# Integrated_Main_Driver_Board-01-Minimum_.net
KiCad netlist of a schematic drawn in Altium Designer
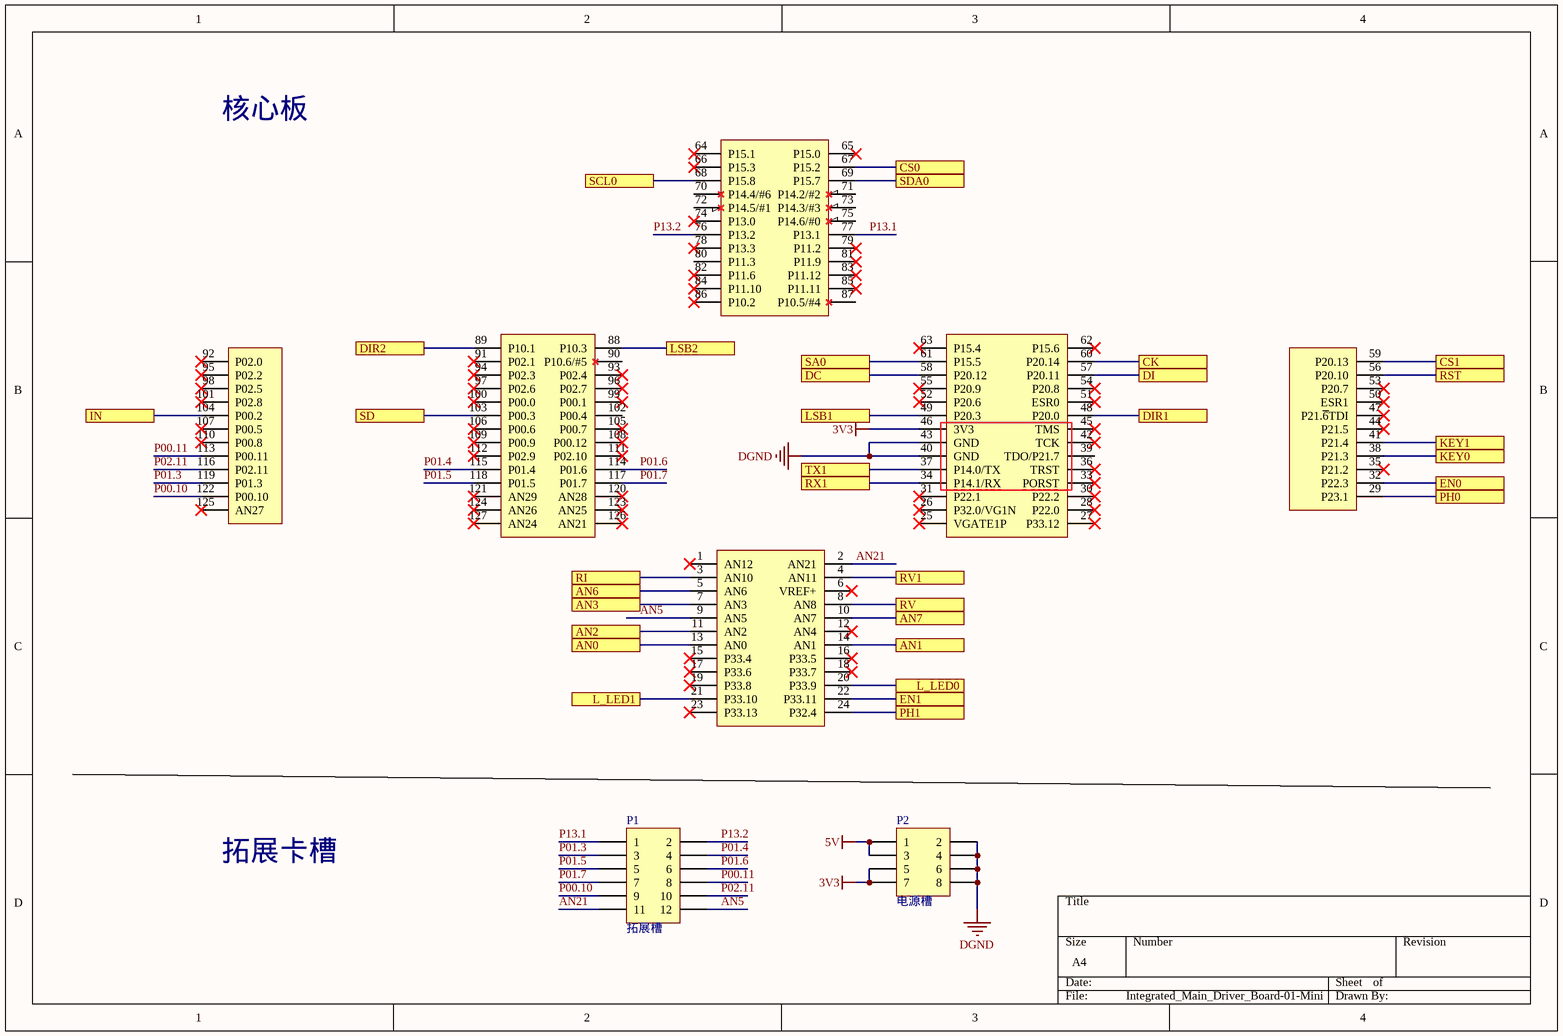
[diagram p0: Integrated_Main_Driver_Board-01-Minimum System Circuit-20230110.SchDoc]

(export (version "E")
  (design (tool "Eeschema 10.0.6"))
  (components
    (comp (ref "LQ-TC1")
      (value "LQ-TC3X7-SYSVB")
      (footprint "TC377")
      (libsource (lib "Schlib1") (part "LQ-TC3X7-SYSVB"))
    )
    (comp (ref "P1")
      (value "拓展槽")
      (footprint "HDR2X6")
      (description "Header, 6-Pin, Dual row")
      (fields (field (name "PUBLISHER") "Altium Limited"))
      (libsource (lib "Miscellaneous Connectors") (part "Header 6X2"))
    )
    (comp (ref "P2")
      (value "电源槽")
      (footprint "HDR2X4")
      (description "Header, 4-Pin, Dual row")
      (fields (field (name "PUBLISHER") "Altium Limited"))
      (libsource (lib "Miscellaneous Connectors") (part "Header 4X2"))
    )
  )
  (nets
    (net (code "1") (name "/AN0") (class "Default")
      (node (ref "LQ-TC1") (pin "13") (pinfunction "AN0_13") (pintype "passive"))
    )
    (net (code "2") (name "/AN1") (class "Default")
      (node (ref "LQ-TC1") (pin "14") (pinfunction "AN1_14") (pintype "passive"))
    )
    (net (code "3") (name "/AN2") (class "Default")
      (node (ref "LQ-TC1") (pin "11") (pinfunction "AN2_11") (pintype "passive"))
    )
    (net (code "4") (name "/AN3") (class "Default")
      (node (ref "LQ-TC1") (pin "7") (pinfunction "AN3_7") (pintype "passive"))
    )
    (net (code "5") (name "/AN5") (class "Default")
      (node (ref "LQ-TC1") (pin "9") (pinfunction "AN5_9") (pintype "passive"))
      (node (ref "P1") (pin "12") (pinfunction "12_12") (pintype "passive"))
    )
    (net (code "6") (name "/AN6") (class "Default")
      (node (ref "LQ-TC1") (pin "5") (pinfunction "AN6_5") (pintype "passive"))
    )
    (net (code "7") (name "/AN7") (class "Default")
      (node (ref "LQ-TC1") (pin "10") (pinfunction "AN7_10") (pintype "passive"))
    )
    (net (code "8") (name "/AN21") (class "Default")
      (node (ref "LQ-TC1") (pin "2") (pinfunction "AN21_2") (pintype "passive"))
      (node (ref "P1") (pin "11") (pinfunction "11_11") (pintype "passive"))
    )
    (net (code "9") (name "/CK") (class "Default")
      (node (ref "LQ-TC1") (pin "60") (pinfunction "P20.14_60") (pintype "passive"))
    )
    (net (code "10") (name "/CS0") (class "Default")
      (node (ref "LQ-TC1") (pin "67") (pinfunction "P15.2_67") (pintype "passive"))
    )
    (net (code "11") (name "/CS1") (class "Default")
      (node (ref "LQ-TC1") (pin "59") (pinfunction "P20.13_59") (pintype "passive"))
    )
    (net (code "12") (name "/DC") (class "Default")
      (node (ref "LQ-TC1") (pin "58") (pinfunction "P20.12_58") (pintype "passive"))
    )
    (net (code "13") (name "/DI") (class "Default")
      (node (ref "LQ-TC1") (pin "57") (pinfunction "P20.11_57") (pintype "passive"))
    )
    (net (code "14") (name "/DIR1") (class "Default")
      (node (ref "LQ-TC1") (pin "48") (pinfunction "P20.0_48") (pintype "passive"))
    )
    (net (code "15") (name "/DIR2") (class "Default")
      (node (ref "LQ-TC1") (pin "89") (pinfunction "P10.1_89") (pintype "passive"))
    )
    (net (code "16") (name "/EN0") (class "Default")
      (node (ref "LQ-TC1") (pin "32") (pinfunction "P22.3_32") (pintype "passive"))
    )
    (net (code "17") (name "/EN1") (class "Default")
      (node (ref "LQ-TC1") (pin "22") (pinfunction "P33.11_22") (pintype "passive"))
    )
    (net (code "18") (name "/IN") (class "Default")
      (node (ref "LQ-TC1") (pin "104") (pinfunction "P00.2_104") (pintype "passive"))
    )
    (net (code "19") (name "/KEY0") (class "Default")
      (node (ref "LQ-TC1") (pin "38") (pinfunction "P21.3_38") (pintype "passive"))
    )
    (net (code "20") (name "/KEY1") (class "Default")
      (node (ref "LQ-TC1") (pin "41") (pinfunction "P21.4_41") (pintype "passive"))
    )
    (net (code "21") (name "/LSB1") (class "Default")
      (node (ref "LQ-TC1") (pin "49") (pinfunction "P20.3_49") (pintype "passive"))
    )
    (net (code "22") (name "/LSB2") (class "Default")
      (node (ref "LQ-TC1") (pin "88") (pinfunction "P10.3_88") (pintype "passive"))
    )
    (net (code "23") (name "/L_LED0") (class "Default")
      (node (ref "LQ-TC1") (pin "20") (pinfunction "P33.9_20") (pintype "passive"))
    )
    (net (code "24") (name "/L_LED1") (class "Default")
      (node (ref "LQ-TC1") (pin "21") (pinfunction "P33.10_21") (pintype "passive"))
    )
    (net (code "25") (name "/P00.10") (class "Default")
      (node (ref "LQ-TC1") (pin "122") (pinfunction "P00.10_122") (pintype "passive"))
      (node (ref "P1") (pin "9") (pinfunction "9_9") (pintype "passive"))
    )
    (net (code "26") (name "/P00.11") (class "Default")
      (node (ref "LQ-TC1") (pin "113") (pinfunction "P00.11_113") (pintype "passive"))
      (node (ref "P1") (pin "8") (pinfunction "8_8") (pintype "passive"))
    )
    (net (code "27") (name "/P01.3") (class "Default")
      (node (ref "LQ-TC1") (pin "119") (pinfunction "P01.3_119") (pintype "passive"))
      (node (ref "P1") (pin "3") (pinfunction "3_3") (pintype "passive"))
    )
    (net (code "28") (name "/P01.4") (class "Default")
      (node (ref "LQ-TC1") (pin "115") (pinfunction "P01.4_115") (pintype "passive"))
      (node (ref "P1") (pin "4") (pinfunction "4_4") (pintype "passive"))
    )
    (net (code "29") (name "/P01.5") (class "Default")
      (node (ref "LQ-TC1") (pin "118") (pinfunction "P01.5_118") (pintype "passive"))
      (node (ref "P1") (pin "5") (pinfunction "5_5") (pintype "passive"))
    )
    (net (code "30") (name "/P01.6") (class "Default")
      (node (ref "LQ-TC1") (pin "114") (pinfunction "P01.6_114") (pintype "passive"))
      (node (ref "P1") (pin "6") (pinfunction "6_6") (pintype "passive"))
    )
    (net (code "31") (name "/P01.7") (class "Default")
      (node (ref "LQ-TC1") (pin "117") (pinfunction "P01.7_117") (pintype "passive"))
      (node (ref "P1") (pin "7") (pinfunction "7_7") (pintype "passive"))
    )
    (net (code "32") (name "/P02.11") (class "Default")
      (node (ref "LQ-TC1") (pin "116") (pinfunction "P02.11_116") (pintype "passive"))
      (node (ref "P1") (pin "10") (pinfunction "10_10") (pintype "passive"))
    )
    (net (code "33") (name "/P13.1") (class "Default")
      (node (ref "LQ-TC1") (pin "77") (pinfunction "P13.1_77") (pintype "passive"))
      (node (ref "P1") (pin "1") (pinfunction "1_1") (pintype "passive"))
    )
    (net (code "34") (name "/P13.2") (class "Default")
      (node (ref "LQ-TC1") (pin "76") (pinfunction "P13.2_76") (pintype "passive"))
      (node (ref "P1") (pin "2") (pinfunction "2_2") (pintype "passive"))
    )
    (net (code "35") (name "/PH0") (class "Default")
      (node (ref "LQ-TC1") (pin "29") (pinfunction "P23.1_29") (pintype "passive"))
    )
    (net (code "36") (name "/PH1") (class "Default")
      (node (ref "LQ-TC1") (pin "24") (pinfunction "P32.4_24") (pintype "passive"))
    )
    (net (code "37") (name "/RI") (class "Default")
      (node (ref "LQ-TC1") (pin "3") (pinfunction "AN10_3") (pintype "passive"))
    )
    (net (code "38") (name "/RST") (class "Default")
      (node (ref "LQ-TC1") (pin "56") (pinfunction "P20.10_56") (pintype "passive"))
    )
    (net (code "39") (name "/RV") (class "Default")
      (node (ref "LQ-TC1") (pin "8") (pinfunction "AN8_8") (pintype "passive"))
    )
    (net (code "40") (name "/RV1") (class "Default")
      (node (ref "LQ-TC1") (pin "4") (pinfunction "AN11_4") (pintype "passive"))
    )
    (net (code "41") (name "/RX1") (class "Default")
      (node (ref "LQ-TC1") (pin "34") (pinfunction "P14.1/RX_34") (pintype "passive"))
    )
    (net (code "42") (name "/SA0") (class "Default")
      (node (ref "LQ-TC1") (pin "61") (pinfunction "P15.5_61") (pintype "passive"))
    )
    (net (code "43") (name "/SCL0") (class "Default")
      (node (ref "LQ-TC1") (pin "68") (pinfunction "P15.8_68") (pintype "passive"))
    )
    (net (code "44") (name "/SD") (class "Default")
      (node (ref "LQ-TC1") (pin "103") (pinfunction "P00.3_103") (pintype "passive"))
    )
    (net (code "45") (name "/SDA0") (class "Default")
      (node (ref "LQ-TC1") (pin "69") (pinfunction "P15.7_69") (pintype "passive"))
    )
    (net (code "46") (name "/TX1") (class "Default")
      (node (ref "LQ-TC1") (pin "37") (pinfunction "P14.0/TX_37") (pintype "passive"))
    )
    (net (code "47") (name "3V3") (class "Default")
      (node (ref "LQ-TC1") (pin "46") (pinfunction "3V3_46") (pintype "passive"))
      (node (ref "P2") (pin "5") (pinfunction "5_5") (pintype "passive"))
      (node (ref "P2") (pin "7") (pinfunction "7_7") (pintype "passive"))
    )
    (net (code "48") (name "5V") (class "Default")
      (node (ref "P2") (pin "1") (pinfunction "1_1") (pintype "passive"))
      (node (ref "P2") (pin "3") (pinfunction "3_3") (pintype "passive"))
    )
    (net (code "49") (name "DGND") (class "Default")
      (node (ref "LQ-TC1") (pin "40") (pinfunction "GND_40") (pintype "passive"))
      (node (ref "LQ-TC1") (pin "43") (pinfunction "GND_43") (pintype "passive"))
      (node (ref "P2") (pin "2") (pinfunction "2_2") (pintype "passive"))
      (node (ref "P2") (pin "4") (pinfunction "4_4") (pintype "passive"))
      (node (ref "P2") (pin "6") (pinfunction "6_6") (pintype "passive"))
      (node (ref "P2") (pin "8") (pinfunction "8_8") (pintype "passive"))
    )
    (net (code "50") (name "unconnected-(LQ-TC1-AN4-Pad12)") (class "Default")
      (node (ref "LQ-TC1") (pin "12") (pinfunction "AN4_12") (pintype "passive+no_connect"))
    )
    (net (code "51") (name "unconnected-(LQ-TC1-AN12-Pad1)") (class "Default")
      (node (ref "LQ-TC1") (pin "1") (pinfunction "AN12_1") (pintype "passive+no_connect"))
    )
    (net (code "52") (name "unconnected-(LQ-TC1-AN21-Pad126)") (class "Default")
      (node (ref "LQ-TC1") (pin "126") (pinfunction "AN21_126") (pintype "passive+no_connect"))
    )
    (net (code "53") (name "unconnected-(LQ-TC1-AN24-Pad127)") (class "Default")
      (node (ref "LQ-TC1") (pin "127") (pinfunction "AN24_127") (pintype "passive+no_connect"))
    )
    (net (code "54") (name "unconnected-(LQ-TC1-AN25-Pad123)") (class "Default")
      (node (ref "LQ-TC1") (pin "123") (pinfunction "AN25_123") (pintype "passive+no_connect"))
    )
    (net (code "55") (name "unconnected-(LQ-TC1-AN26-Pad124)") (class "Default")
      (node (ref "LQ-TC1") (pin "124") (pinfunction "AN26_124") (pintype "passive+no_connect"))
    )
    (net (code "56") (name "unconnected-(LQ-TC1-AN27-Pad125)") (class "Default")
      (node (ref "LQ-TC1") (pin "125") (pinfunction "AN27_125") (pintype "passive+no_connect"))
    )
    (net (code "57") (name "unconnected-(LQ-TC1-AN28-Pad120)") (class "Default")
      (node (ref "LQ-TC1") (pin "120") (pinfunction "AN28_120") (pintype "passive+no_connect"))
    )
    (net (code "58") (name "unconnected-(LQ-TC1-AN29-Pad121)") (class "Default")
      (node (ref "LQ-TC1") (pin "121") (pinfunction "AN29_121") (pintype "passive+no_connect"))
    )
    (net (code "59") (name "unconnected-(LQ-TC1-ESR0-Pad51)") (class "Default")
      (node (ref "LQ-TC1") (pin "51") (pinfunction "ESR0_51") (pintype "passive+no_connect"))
    )
    (net (code "60") (name "unconnected-(LQ-TC1-ESR1-Pad50)") (class "Default")
      (node (ref "LQ-TC1") (pin "50") (pinfunction "ESR1_50") (pintype "passive+no_connect"))
    )
    (net (code "61") (name "unconnected-(LQ-TC1-P00.0-Pad100)") (class "Default")
      (node (ref "LQ-TC1") (pin "100") (pinfunction "P00.0_100") (pintype "passive+no_connect"))
    )
    (net (code "62") (name "unconnected-(LQ-TC1-P00.1-Pad99)") (class "Default")
      (node (ref "LQ-TC1") (pin "99") (pinfunction "P00.1_99") (pintype "passive+no_connect"))
    )
    (net (code "63") (name "unconnected-(LQ-TC1-P00.4-Pad102)") (class "Default")
      (node (ref "LQ-TC1") (pin "102") (pinfunction "P00.4_102") (pintype "passive"))
    )
    (net (code "64") (name "unconnected-(LQ-TC1-P00.5-Pad107)") (class "Default")
      (node (ref "LQ-TC1") (pin "107") (pinfunction "P00.5_107") (pintype "passive+no_connect"))
    )
    (net (code "65") (name "unconnected-(LQ-TC1-P00.6-Pad106)") (class "Default")
      (node (ref "LQ-TC1") (pin "106") (pinfunction "P00.6_106") (pintype "passive+no_connect"))
    )
    (net (code "66") (name "unconnected-(LQ-TC1-P00.7-Pad105)") (class "Default")
      (node (ref "LQ-TC1") (pin "105") (pinfunction "P00.7_105") (pintype "passive+no_connect"))
    )
    (net (code "67") (name "unconnected-(LQ-TC1-P00.8-Pad110)") (class "Default")
      (node (ref "LQ-TC1") (pin "110") (pinfunction "P00.8_110") (pintype "passive+no_connect"))
    )
    (net (code "68") (name "unconnected-(LQ-TC1-P00.9-Pad109)") (class "Default")
      (node (ref "LQ-TC1") (pin "109") (pinfunction "P00.9_109") (pintype "passive+no_connect"))
    )
    (net (code "69") (name "unconnected-(LQ-TC1-P00.12-Pad108)") (class "Default")
      (node (ref "LQ-TC1") (pin "108") (pinfunction "P00.12_108") (pintype "passive+no_connect"))
    )
    (net (code "70") (name "unconnected-(LQ-TC1-P02.0-Pad92)") (class "Default")
      (node (ref "LQ-TC1") (pin "92") (pinfunction "P02.0_92") (pintype "passive+no_connect"))
    )
    (net (code "71") (name "unconnected-(LQ-TC1-P02.1-Pad91)") (class "Default")
      (node (ref "LQ-TC1") (pin "91") (pinfunction "P02.1_91") (pintype "passive+no_connect"))
    )
    (net (code "72") (name "unconnected-(LQ-TC1-P02.2-Pad95)") (class "Default")
      (node (ref "LQ-TC1") (pin "95") (pinfunction "P02.2_95") (pintype "passive+no_connect"))
    )
    (net (code "73") (name "unconnected-(LQ-TC1-P02.3-Pad94)") (class "Default")
      (node (ref "LQ-TC1") (pin "94") (pinfunction "P02.3_94") (pintype "passive+no_connect"))
    )
    (net (code "74") (name "unconnected-(LQ-TC1-P02.4-Pad93)") (class "Default")
      (node (ref "LQ-TC1") (pin "93") (pinfunction "P02.4_93") (pintype "passive+no_connect"))
    )
    (net (code "75") (name "unconnected-(LQ-TC1-P02.5-Pad98)") (class "Default")
      (node (ref "LQ-TC1") (pin "98") (pinfunction "P02.5_98") (pintype "passive+no_connect"))
    )
    (net (code "76") (name "unconnected-(LQ-TC1-P02.6-Pad97)") (class "Default")
      (node (ref "LQ-TC1") (pin "97") (pinfunction "P02.6_97") (pintype "passive+no_connect"))
    )
    (net (code "77") (name "unconnected-(LQ-TC1-P02.7-Pad96)") (class "Default")
      (node (ref "LQ-TC1") (pin "96") (pinfunction "P02.7_96") (pintype "passive+no_connect"))
    )
    (net (code "78") (name "unconnected-(LQ-TC1-P02.8-Pad101)") (class "Default")
      (node (ref "LQ-TC1") (pin "101") (pinfunction "P02.8_101") (pintype "passive+no_connect"))
    )
    (net (code "79") (name "unconnected-(LQ-TC1-P02.9-Pad112)") (class "Default")
      (node (ref "LQ-TC1") (pin "112") (pinfunction "P02.9_112") (pintype "passive+no_connect"))
    )
    (net (code "80") (name "unconnected-(LQ-TC1-P02.10-Pad111)") (class "Default")
      (node (ref "LQ-TC1") (pin "111") (pinfunction "P02.10_111") (pintype "passive+no_connect"))
    )
    (net (code "81") (name "unconnected-(LQ-TC1-P10.2-Pad86)") (class "Default")
      (node (ref "LQ-TC1") (pin "86") (pinfunction "P10.2_86") (pintype "passive+no_connect"))
    )
    (net (code "82") (name "unconnected-(LQ-TC1-P10.5{slash}#4-Pad87)") (class "Default")
      (node (ref "LQ-TC1") (pin "87") (pinfunction "P10.5/#4_87") (pintype "passive"))
    )
    (net (code "83") (name "unconnected-(LQ-TC1-P10.6{slash}#5-Pad90)") (class "Default")
      (node (ref "LQ-TC1") (pin "90") (pinfunction "P10.6/#5_90") (pintype "passive"))
    )
    (net (code "84") (name "unconnected-(LQ-TC1-P11.2-Pad79)") (class "Default")
      (node (ref "LQ-TC1") (pin "79") (pinfunction "P11.2_79") (pintype "passive+no_connect"))
    )
    (net (code "85") (name "unconnected-(LQ-TC1-P11.3-Pad80)") (class "Default")
      (node (ref "LQ-TC1") (pin "80") (pinfunction "P11.3_80") (pintype "passive"))
    )
    (net (code "86") (name "unconnected-(LQ-TC1-P11.6-Pad82)") (class "Default")
      (node (ref "LQ-TC1") (pin "82") (pinfunction "P11.6_82") (pintype "passive+no_connect"))
    )
    (net (code "87") (name "unconnected-(LQ-TC1-P11.9-Pad81)") (class "Default")
      (node (ref "LQ-TC1") (pin "81") (pinfunction "P11.9_81") (pintype "passive+no_connect"))
    )
    (net (code "88") (name "unconnected-(LQ-TC1-P11.10-Pad84)") (class "Default")
      (node (ref "LQ-TC1") (pin "84") (pinfunction "P11.10_84") (pintype "passive+no_connect"))
    )
    (net (code "89") (name "unconnected-(LQ-TC1-P11.11-Pad85)") (class "Default")
      (node (ref "LQ-TC1") (pin "85") (pinfunction "P11.11_85") (pintype "passive+no_connect"))
    )
    (net (code "90") (name "unconnected-(LQ-TC1-P11.12-Pad83)") (class "Default")
      (node (ref "LQ-TC1") (pin "83") (pinfunction "P11.12_83") (pintype "passive+no_connect"))
    )
    (net (code "91") (name "unconnected-(LQ-TC1-P13.0-Pad74)") (class "Default")
      (node (ref "LQ-TC1") (pin "74") (pinfunction "P13.0_74") (pintype "passive+no_connect"))
    )
    (net (code "92") (name "unconnected-(LQ-TC1-P13.3-Pad78)") (class "Default")
      (node (ref "LQ-TC1") (pin "78") (pinfunction "P13.3_78") (pintype "passive+no_connect"))
    )
    (net (code "93") (name "unconnected-(LQ-TC1-P14.2{slash}#2-Pad71)") (class "Default")
      (node (ref "LQ-TC1") (pin "71") (pinfunction "P14.2/#2_71") (pintype "passive"))
    )
    (net (code "94") (name "unconnected-(LQ-TC1-P14.3{slash}#3-Pad73)") (class "Default")
      (node (ref "LQ-TC1") (pin "73") (pinfunction "P14.3/#3_73") (pintype "passive"))
    )
    (net (code "95") (name "unconnected-(LQ-TC1-P14.4{slash}#6-Pad70)") (class "Default")
      (node (ref "LQ-TC1") (pin "70") (pinfunction "P14.4/#6_70") (pintype "passive"))
    )
    (net (code "96") (name "unconnected-(LQ-TC1-P14.5{slash}#1-Pad72)") (class "Default")
      (node (ref "LQ-TC1") (pin "72") (pinfunction "P14.5/#1_72") (pintype "passive"))
    )
    (net (code "97") (name "unconnected-(LQ-TC1-P14.6{slash}#0-Pad75)") (class "Default")
      (node (ref "LQ-TC1") (pin "75") (pinfunction "P14.6/#0_75") (pintype "passive"))
    )
    (net (code "98") (name "unconnected-(LQ-TC1-P15.0-Pad65)") (class "Default")
      (node (ref "LQ-TC1") (pin "65") (pinfunction "P15.0_65") (pintype "passive+no_connect"))
    )
    (net (code "99") (name "unconnected-(LQ-TC1-P15.1-Pad64)") (class "Default")
      (node (ref "LQ-TC1") (pin "64") (pinfunction "P15.1_64") (pintype "passive+no_connect"))
    )
    (net (code "100") (name "unconnected-(LQ-TC1-P15.3-Pad66)") (class "Default")
      (node (ref "LQ-TC1") (pin "66") (pinfunction "P15.3_66") (pintype "passive+no_connect"))
    )
    (net (code "101") (name "unconnected-(LQ-TC1-P15.4-Pad63)") (class "Default")
      (node (ref "LQ-TC1") (pin "63") (pinfunction "P15.4_63") (pintype "passive+no_connect"))
    )
    (net (code "102") (name "unconnected-(LQ-TC1-P15.6-Pad62)") (class "Default")
      (node (ref "LQ-TC1") (pin "62") (pinfunction "P15.6_62") (pintype "passive+no_connect"))
    )
    (net (code "103") (name "unconnected-(LQ-TC1-P20.6-Pad52)") (class "Default")
      (node (ref "LQ-TC1") (pin "52") (pinfunction "P20.6_52") (pintype "passive+no_connect"))
    )
    (net (code "104") (name "unconnected-(LQ-TC1-P20.7-Pad53)") (class "Default")
      (node (ref "LQ-TC1") (pin "53") (pinfunction "P20.7_53") (pintype "passive+no_connect"))
    )
    (net (code "105") (name "unconnected-(LQ-TC1-P20.8-Pad54)") (class "Default")
      (node (ref "LQ-TC1") (pin "54") (pinfunction "P20.8_54") (pintype "passive+no_connect"))
    )
    (net (code "106") (name "unconnected-(LQ-TC1-P20.9-Pad55)") (class "Default")
      (node (ref "LQ-TC1") (pin "55") (pinfunction "P20.9_55") (pintype "passive+no_connect"))
    )
    (net (code "107") (name "unconnected-(LQ-TC1-P21.2-Pad35)") (class "Default")
      (node (ref "LQ-TC1") (pin "35") (pinfunction "P21.2_35") (pintype "passive+no_connect"))
    )
    (net (code "108") (name "unconnected-(LQ-TC1-P21.5-Pad44)") (class "Default")
      (node (ref "LQ-TC1") (pin "44") (pinfunction "P21.5_44") (pintype "passive+no_connect"))
    )
    (net (code "109") (name "unconnected-(LQ-TC1-P21.~{6}TDI-Pad47)") (class "Default")
      (node (ref "LQ-TC1") (pin "47") (pinfunction "P21.~{6}TDI_47") (pintype "passive+no_connect"))
    )
    (net (code "110") (name "unconnected-(LQ-TC1-P22.0-Pad28)") (class "Default")
      (node (ref "LQ-TC1") (pin "28") (pinfunction "P22.0_28") (pintype "passive+no_connect"))
    )
    (net (code "111") (name "unconnected-(LQ-TC1-P22.1-Pad31)") (class "Default")
      (node (ref "LQ-TC1") (pin "31") (pinfunction "P22.1_31") (pintype "passive+no_connect"))
    )
    (net (code "112") (name "unconnected-(LQ-TC1-P22.2-Pad30)") (class "Default")
      (node (ref "LQ-TC1") (pin "30") (pinfunction "P22.2_30") (pintype "passive+no_connect"))
    )
    (net (code "113") (name "unconnected-(LQ-TC1-P32.0{slash}VG1N-Pad26)") (class "Default")
      (node (ref "LQ-TC1") (pin "26") (pinfunction "P32.0/VG1N_26") (pintype "passive+no_connect"))
    )
    (net (code "114") (name "unconnected-(LQ-TC1-P33.4-Pad15)") (class "Default")
      (node (ref "LQ-TC1") (pin "15") (pinfunction "P33.4_15") (pintype "passive+no_connect"))
    )
    (net (code "115") (name "unconnected-(LQ-TC1-P33.5-Pad16)") (class "Default")
      (node (ref "LQ-TC1") (pin "16") (pinfunction "P33.5_16") (pintype "passive+no_connect"))
    )
    (net (code "116") (name "unconnected-(LQ-TC1-P33.6-Pad17)") (class "Default")
      (node (ref "LQ-TC1") (pin "17") (pinfunction "P33.6_17") (pintype "passive+no_connect"))
    )
    (net (code "117") (name "unconnected-(LQ-TC1-P33.7-Pad18)") (class "Default")
      (node (ref "LQ-TC1") (pin "18") (pinfunction "P33.7_18") (pintype "passive+no_connect"))
    )
    (net (code "118") (name "unconnected-(LQ-TC1-P33.8-Pad19)") (class "Default")
      (node (ref "LQ-TC1") (pin "19") (pinfunction "P33.8_19") (pintype "passive+no_connect"))
    )
    (net (code "119") (name "unconnected-(LQ-TC1-P33.12-Pad27)") (class "Default")
      (node (ref "LQ-TC1") (pin "27") (pinfunction "P33.12_27") (pintype "passive+no_connect"))
    )
    (net (code "120") (name "unconnected-(LQ-TC1-P33.13-Pad23)") (class "Default")
      (node (ref "LQ-TC1") (pin "23") (pinfunction "P33.13_23") (pintype "passive+no_connect"))
    )
    (net (code "121") (name "unconnected-(LQ-TC1-PORST-Pad33)") (class "Default")
      (node (ref "LQ-TC1") (pin "33") (pinfunction "PORST_33") (pintype "passive+no_connect"))
    )
    (net (code "122") (name "unconnected-(LQ-TC1-TCK-Pad42)") (class "Default")
      (node (ref "LQ-TC1") (pin "42") (pinfunction "TCK_42") (pintype "passive+no_connect"))
    )
    (net (code "123") (name "unconnected-(LQ-TC1-TDO{slash}P21.7-Pad39)") (class "Default")
      (node (ref "LQ-TC1") (pin "39") (pinfunction "TDO/P21.7_39") (pintype "passive"))
    )
    (net (code "124") (name "unconnected-(LQ-TC1-TMS-Pad45)") (class "Default")
      (node (ref "LQ-TC1") (pin "45") (pinfunction "TMS_45") (pintype "passive+no_connect"))
    )
    (net (code "125") (name "unconnected-(LQ-TC1-TRST-Pad36)") (class "Default")
      (node (ref "LQ-TC1") (pin "36") (pinfunction "TRST_36") (pintype "passive+no_connect"))
    )
    (net (code "126") (name "unconnected-(LQ-TC1-VGATE1P-Pad25)") (class "Default")
      (node (ref "LQ-TC1") (pin "25") (pinfunction "VGATE1P_25") (pintype "passive+no_connect"))
    )
    (net (code "127") (name "unconnected-(LQ-TC1-VREF+-Pad6)") (class "Default")
      (node (ref "LQ-TC1") (pin "6") (pinfunction "VREF+_6") (pintype "passive+no_connect"))
    )
  )
)
